# ECAT1__OUT.net
KiCad netlist of a schematic drawn in Altium Designer
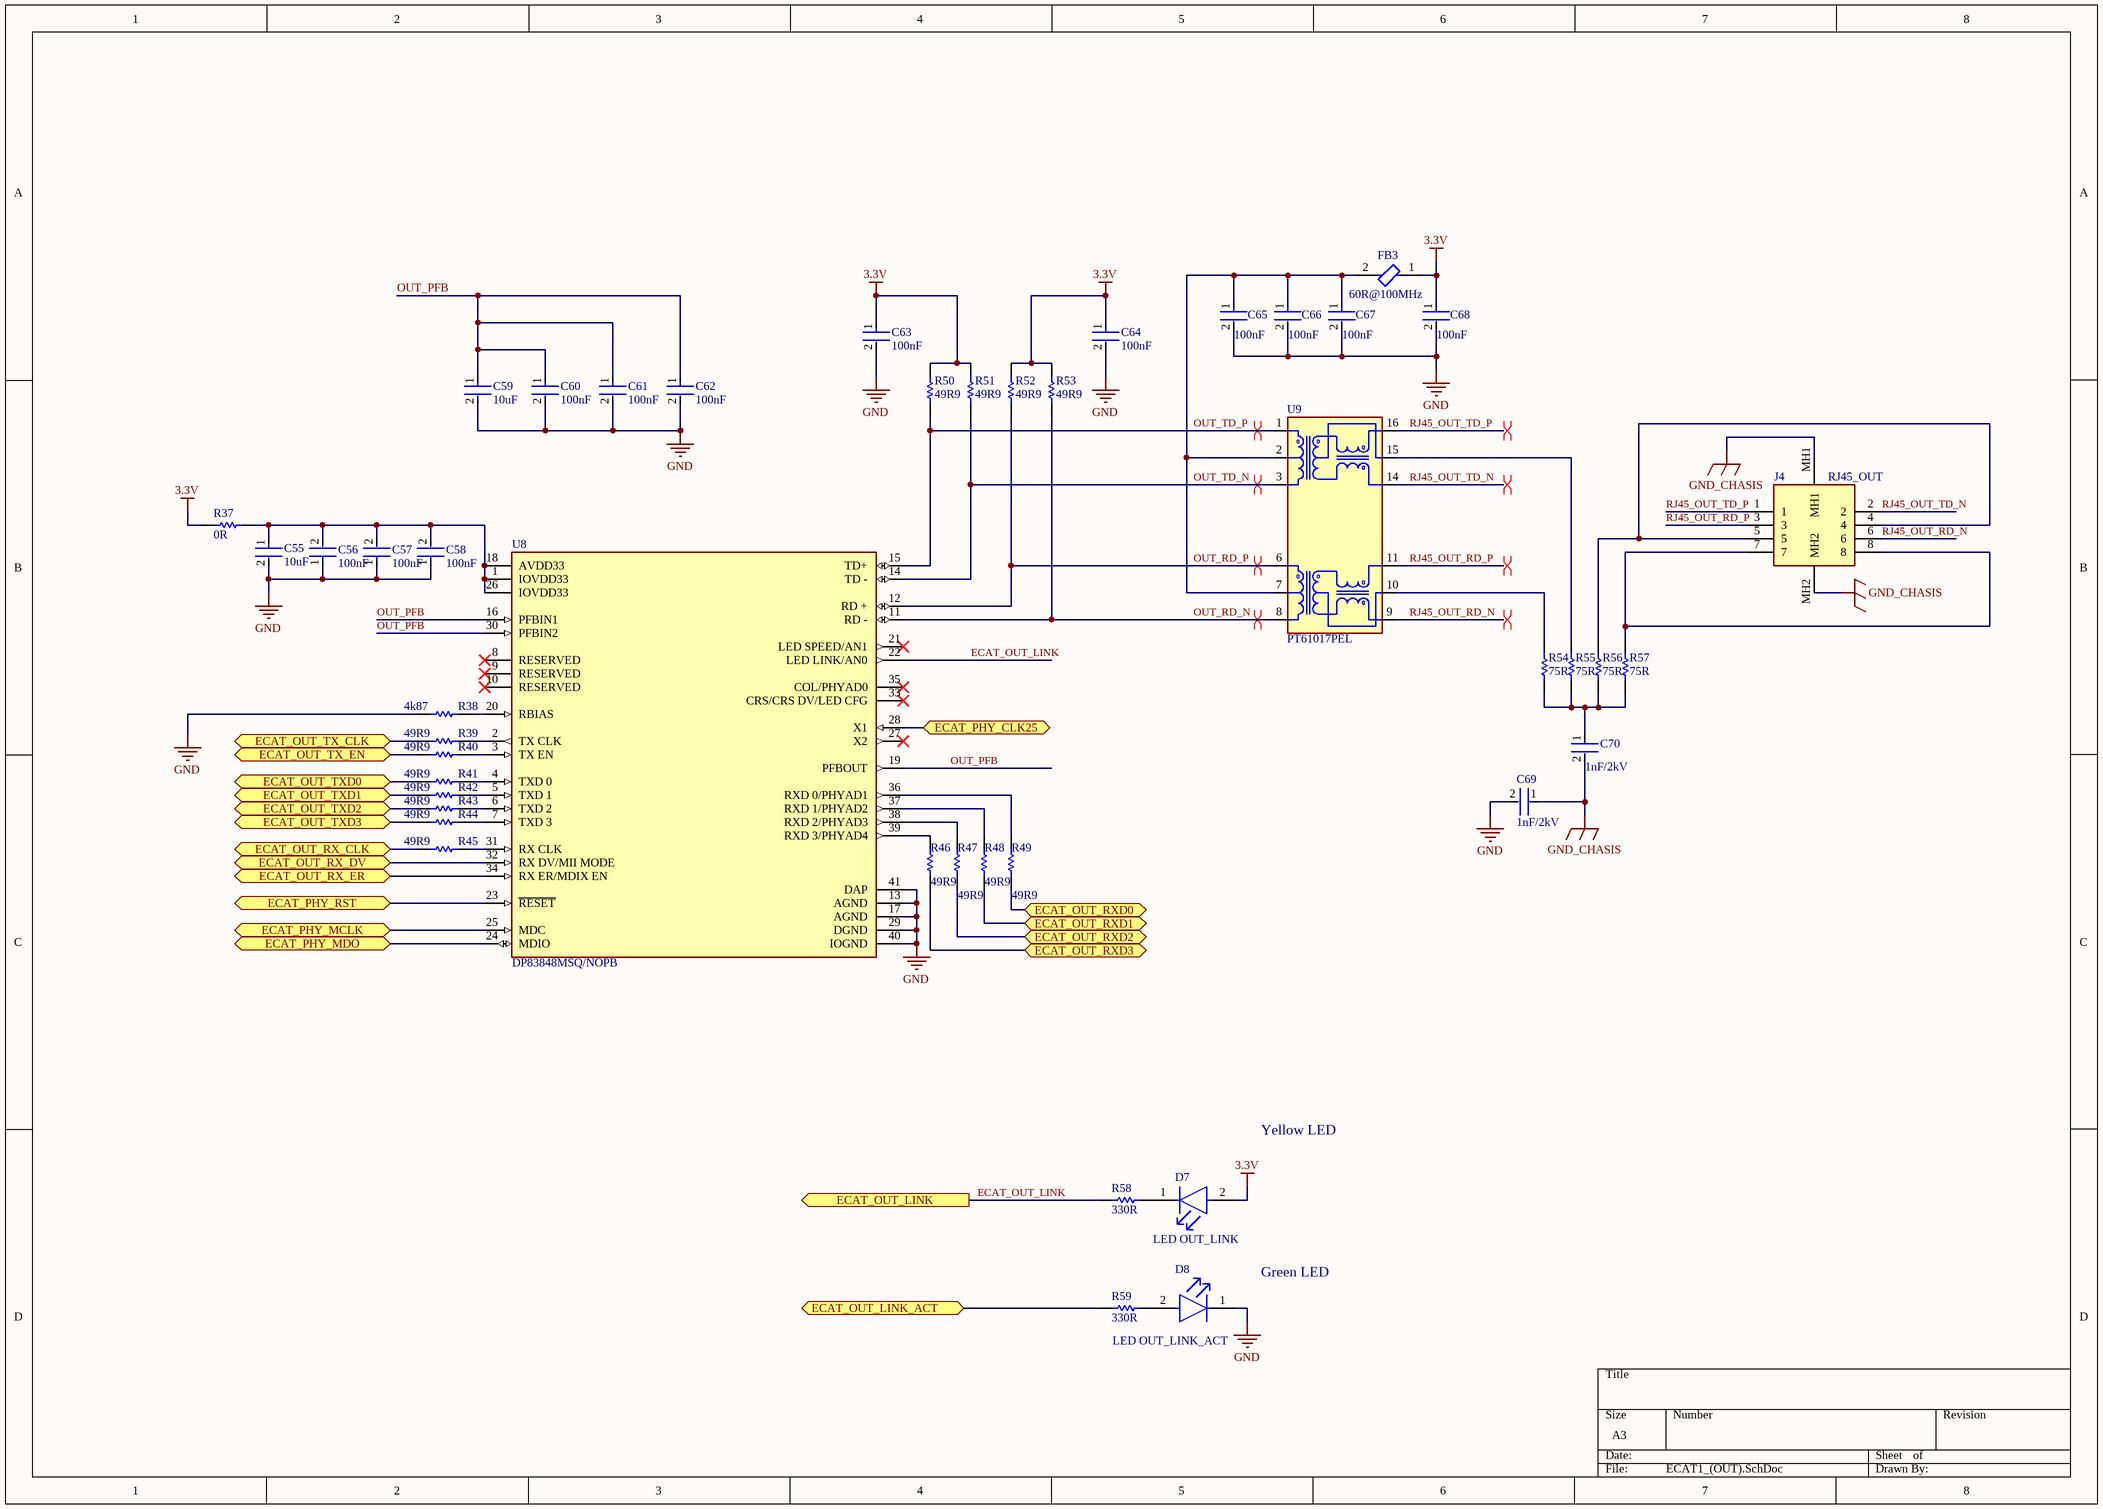
[diagram p0: ECAT1_(OUT).SchDoc]

(export (version "E")
  (design (tool "Eeschema 10.0.6"))
  (components
    (comp (ref "C55")
      (value "10uF")
      (footprint "FP-C0805C-DN-MFG")
      (description "CAP CER 0.1UF 50V X7R 0805")
      (fields
        (field (name "MANUFACTURER PART NUMBER") "C0805C104K5RACTU")
        (field (name "MANUFACTURER") "KEMET")
      )
      (libsource (lib "Altium Content Vault") (part "b4654b650e69147ec39a6b967a45e02"))
    )
    (comp (ref "C56")
      (value "100nF")
      (footprint "FP-C0805C-DN-MFG")
      (description "CAP CER 0.1UF 50V X7R 0805")
      (fields
        (field (name "MANUFACTURER PART NUMBER") "C0805C104K5RACTU")
        (field (name "MANUFACTURER") "KEMET")
      )
      (libsource (lib "Altium Content Vault") (part "b4654b650e69147ec39a6b967a45e02"))
    )
    (comp (ref "C57")
      (value "100nF")
      (footprint "FP-C0805C-DN-MFG")
      (description "CAP CER 0.1UF 50V X7R 0805")
      (fields
        (field (name "MANUFACTURER PART NUMBER") "C0805C104K5RACTU")
        (field (name "MANUFACTURER") "KEMET")
      )
      (libsource (lib "Altium Content Vault") (part "b4654b650e69147ec39a6b967a45e02"))
    )
    (comp (ref "C58")
      (value "100nF")
      (footprint "FP-C0805C-DN-MFG")
      (description "CAP CER 0.1UF 50V X7R 0805")
      (fields
        (field (name "MANUFACTURER PART NUMBER") "C0805C104K5RACTU")
        (field (name "MANUFACTURER") "KEMET")
      )
      (libsource (lib "Altium Content Vault") (part "b4654b650e69147ec39a6b967a45e02"))
    )
    (comp (ref "C59")
      (value "10uF")
      (footprint "FP-C0805C-DN-MFG")
      (description "CAP CER 0.1UF 50V X7R 0805")
      (fields
        (field (name "MANUFACTURER PART NUMBER") "C0805C104K5RACTU")
        (field (name "MANUFACTURER") "KEMET")
      )
      (libsource (lib "Altium Content Vault") (part "b4654b650e69147ec39a6b967a45e02"))
    )
    (comp (ref "C60")
      (value "100nF")
      (footprint "FP-C0805C-DN-MFG")
      (description "CAP CER 0.1UF 50V X7R 0805")
      (fields
        (field (name "MANUFACTURER PART NUMBER") "C0805C104K5RACTU")
        (field (name "MANUFACTURER") "KEMET")
      )
      (libsource (lib "Altium Content Vault") (part "b4654b650e69147ec39a6b967a45e02"))
    )
    (comp (ref "C61")
      (value "100nF")
      (footprint "FP-C0805C-DN-MFG")
      (description "CAP CER 0.1UF 50V X7R 0805")
      (fields
        (field (name "MANUFACTURER PART NUMBER") "C0805C104K5RACTU")
        (field (name "MANUFACTURER") "KEMET")
      )
      (libsource (lib "Altium Content Vault") (part "b4654b650e69147ec39a6b967a45e02"))
    )
    (comp (ref "C62")
      (value "100nF")
      (footprint "FP-C0805C-DN-MFG")
      (description "CAP CER 0.1UF 50V X7R 0805")
      (fields
        (field (name "MANUFACTURER PART NUMBER") "C0805C104K5RACTU")
        (field (name "MANUFACTURER") "KEMET")
      )
      (libsource (lib "Altium Content Vault") (part "b4654b650e69147ec39a6b967a45e02"))
    )
    (comp (ref "C63")
      (value "100nF")
      (footprint "FP-C0805C-DN-MFG")
      (description "CAP CER 0.1UF 50V X7R 0805")
      (fields
        (field (name "MANUFACTURER PART NUMBER") "C0805C104K5RACTU")
        (field (name "MANUFACTURER") "KEMET")
      )
      (libsource (lib "Altium Content Vault") (part "b4654b650e69147ec39a6b967a45e02"))
    )
    (comp (ref "C64")
      (value "100nF")
      (footprint "FP-C0805C-DN-MFG")
      (description "CAP CER 0.1UF 50V X7R 0805")
      (fields
        (field (name "MANUFACTURER PART NUMBER") "C0805C104K5RACTU")
        (field (name "MANUFACTURER") "KEMET")
      )
      (libsource (lib "Altium Content Vault") (part "b4654b650e69147ec39a6b967a45e02"))
    )
    (comp (ref "C65")
      (value "100nF")
      (footprint "FP-C0805C-DN-MFG")
      (description "CAP CER 0.1UF 50V X7R 0805")
      (fields
        (field (name "MANUFACTURER PART NUMBER") "C0805C104K5RACTU")
        (field (name "MANUFACTURER") "KEMET")
      )
      (libsource (lib "Altium Content Vault") (part "b4654b650e69147ec39a6b967a45e02"))
    )
    (comp (ref "C66")
      (value "100nF")
      (footprint "FP-C0805C-DN-MFG")
      (description "CAP CER 0.1UF 50V X7R 0805")
      (fields
        (field (name "MANUFACTURER PART NUMBER") "C0805C104K5RACTU")
        (field (name "MANUFACTURER") "KEMET")
      )
      (libsource (lib "Altium Content Vault") (part "b4654b650e69147ec39a6b967a45e02"))
    )
    (comp (ref "C67")
      (value "100nF")
      (footprint "FP-C0805C-DN-MFG")
      (description "CAP CER 0.1UF 50V X7R 0805")
      (fields
        (field (name "MANUFACTURER PART NUMBER") "C0805C104K5RACTU")
        (field (name "MANUFACTURER") "KEMET")
      )
      (libsource (lib "Altium Content Vault") (part "b4654b650e69147ec39a6b967a45e02"))
    )
    (comp (ref "C68")
      (value "100nF")
      (footprint "FP-C0805C-DN-MFG")
      (description "CAP CER 0.1UF 50V X7R 0805")
      (fields
        (field (name "MANUFACTURER PART NUMBER") "C0805C104K5RACTU")
        (field (name "MANUFACTURER") "KEMET")
      )
      (libsource (lib "Altium Content Vault") (part "b4654b650e69147ec39a6b967a45e02"))
    )
    (comp (ref "C69")
      (value "1nF/2kV")
      (footprint "FP-CC1206-0_3-1_45-IPC_C")
      (description "1nF/2kV/1206")
      (fields (field (name "TOLERANCE") "10%") (field (name "VOLTAGE") "2kV"))
      (libsource (lib "Altium Content Vault") (part "02cd4be3c70576c341d710602a673aa"))
    )
    (comp (ref "C70")
      (value "1nF/2kV")
      (footprint "FP-CC1206-0_3-1_45-IPC_C")
      (description "1nF/2kV/1206")
      (fields (field (name "TOLERANCE") "10%") (field (name "VOLTAGE") "2kV"))
      (libsource (lib "Altium Content Vault") (part "02cd4be3c70576c341d710602a673aa"))
    )
    (comp (ref "D7")
      (value "LED OUT_LINK")
      (footprint "FP-LTST-C191GKT-MFG")
      (description "KPHD-1608LVSYCK")
      (libsource (lib "Altium Content Vault") (part "8706943c75ba83719d021d2fdc84c58"))
    )
    (comp (ref "D8")
      (value "LED OUT_LINK_ACT")
      (footprint "FP-LTST-C191GKT-MFG")
      (description "KPHD-1608LVCGCK")
      (libsource (lib "Altium Content Vault") (part "8706943c75ba83719d021d2fdc84c58"))
    )
    (comp (ref "FB3")
      (value "60R@100MHz")
      (footprint "FP-BLM18-0_15-t0_8-IPC_B")
      (description "Chip Ferrite Bead, 0603, 60Ω @ 100MHz, 0.1Ω, , 1A")
      (fields (field (name "TOLERANCE") "25%"))
      (libsource (lib "Altium Content Vault") (part "5f30dd21d616792df468990f7003faa"))
    )
    (comp (ref "J4")
      (value "RJ45_OUT")
      (footprint "438600010")
      (fields
        (field (name "MOUSER PART NUMBER") "538-43860-0010")
        (field (name "MANUFACTURER_PART_NUMBER") "43860-0010")
      )
      (libsource (lib "43860-0010_RJ45") (part "43860-0010"))
    )
    (comp (ref "R37")
      (value "0R")
      (footprint "RESC1609X50X30NL8T20")
      (description "0603")
      (fields (field (name "MANUFACTURER") "Vishay Semiconductor"))
      (libsource (lib "Altium Content Vault") (part "RES-2"))
    )
    (comp (ref "R38")
      (value "4k87")
      (footprint "RESC2013X50X30LL20T20")
      (description "0805")
      (fields (field (name "MANUFACTURER") "Vishay Dale") (field (name "PART NUMBER") "CRCW08050000Z0EA"))
      (libsource (lib "Altium Content Vault") (part "RES"))
    )
    (comp (ref "R39")
      (value "49R9")
      (footprint "RESC2013X50X30LL20T20")
      (description "0805")
      (fields (field (name "MANUFACTURER") "Vishay Dale") (field (name "PART NUMBER") "CRCW08050000Z0EA"))
      (libsource (lib "Altium Content Vault") (part "RES"))
    )
    (comp (ref "R40")
      (value "49R9")
      (footprint "RESC2013X50X30LL20T20")
      (description "0805")
      (fields (field (name "MANUFACTURER") "Vishay Dale") (field (name "PART NUMBER") "CRCW08050000Z0EA"))
      (libsource (lib "Altium Content Vault") (part "RES"))
    )
    (comp (ref "R41")
      (value "49R9")
      (footprint "RESC2013X50X30LL20T20")
      (description "0805")
      (fields (field (name "MANUFACTURER") "Vishay Dale") (field (name "PART NUMBER") "CRCW08050000Z0EA"))
      (libsource (lib "Altium Content Vault") (part "RES"))
    )
    (comp (ref "R42")
      (value "49R9")
      (footprint "RESC2013X50X30LL20T20")
      (description "0805")
      (fields (field (name "MANUFACTURER") "Vishay Dale") (field (name "PART NUMBER") "CRCW08050000Z0EA"))
      (libsource (lib "Altium Content Vault") (part "RES"))
    )
    (comp (ref "R43")
      (value "49R9")
      (footprint "RESC2013X50X30LL20T20")
      (description "0805")
      (fields (field (name "MANUFACTURER") "Vishay Dale") (field (name "PART NUMBER") "CRCW08050000Z0EA"))
      (libsource (lib "Altium Content Vault") (part "RES"))
    )
    (comp (ref "R44")
      (value "49R9")
      (footprint "RESC2013X50X30LL20T20")
      (description "0805")
      (fields (field (name "MANUFACTURER") "Vishay Dale") (field (name "PART NUMBER") "CRCW08050000Z0EA"))
      (libsource (lib "Altium Content Vault") (part "RES"))
    )
    (comp (ref "R45")
      (value "49R9")
      (footprint "RESC2013X50X30LL20T20")
      (description "0805")
      (fields (field (name "MANUFACTURER") "Vishay Dale") (field (name "PART NUMBER") "CRCW08050000Z0EA"))
      (libsource (lib "Altium Content Vault") (part "RES"))
    )
    (comp (ref "R46")
      (value "49R9")
      (footprint "RESC2013X50X30LL20T20")
      (description "0805")
      (fields (field (name "MANUFACTURER") "Vishay Dale") (field (name "PART NUMBER") "CRCW08050000Z0EA"))
      (libsource (lib "Altium Content Vault") (part "RES"))
    )
    (comp (ref "R47")
      (value "49R9")
      (footprint "RESC2013X50X30LL20T20")
      (description "0805")
      (fields (field (name "MANUFACTURER") "Vishay Dale") (field (name "PART NUMBER") "CRCW08050000Z0EA"))
      (libsource (lib "Altium Content Vault") (part "RES"))
    )
    (comp (ref "R48")
      (value "49R9")
      (footprint "RESC2013X50X30LL20T20")
      (description "0805")
      (fields (field (name "MANUFACTURER") "Vishay Dale") (field (name "PART NUMBER") "CRCW08050000Z0EA"))
      (libsource (lib "Altium Content Vault") (part "RES"))
    )
    (comp (ref "R49")
      (value "49R9")
      (footprint "RESC2013X50X30LL20T20")
      (description "0805")
      (fields (field (name "MANUFACTURER") "Vishay Dale") (field (name "PART NUMBER") "CRCW08050000Z0EA"))
      (libsource (lib "Altium Content Vault") (part "RES"))
    )
    (comp (ref "R50")
      (value "49R9")
      (footprint "RESC2013X50X30LL20T20")
      (description "0805")
      (fields (field (name "MANUFACTURER") "Vishay Dale") (field (name "PART NUMBER") "CRCW08050000Z0EA"))
      (libsource (lib "Altium Content Vault") (part "RES"))
    )
    (comp (ref "R51")
      (value "49R9")
      (footprint "RESC2013X50X30LL20T20")
      (description "0805")
      (fields (field (name "MANUFACTURER") "Vishay Dale") (field (name "PART NUMBER") "CRCW08050000Z0EA"))
      (libsource (lib "Altium Content Vault") (part "RES"))
    )
    (comp (ref "R52")
      (value "49R9")
      (footprint "RESC2013X50X30LL20T20")
      (description "0805")
      (fields (field (name "MANUFACTURER") "Vishay Dale") (field (name "PART NUMBER") "CRCW08050000Z0EA"))
      (libsource (lib "Altium Content Vault") (part "RES"))
    )
    (comp (ref "R53")
      (value "49R9")
      (footprint "RESC2013X50X30LL20T20")
      (description "0805")
      (fields (field (name "MANUFACTURER") "Vishay Dale") (field (name "PART NUMBER") "CRCW08050000Z0EA"))
      (libsource (lib "Altium Content Vault") (part "RES"))
    )
    (comp (ref "R54")
      (value "75R")
      (footprint "RESC2013X50X30LL20T20")
      (description "0805")
      (fields (field (name "MANUFACTURER") "Vishay Dale") (field (name "PART NUMBER") "CRCW08050000Z0EA"))
      (libsource (lib "Altium Content Vault") (part "RES"))
    )
    (comp (ref "R55")
      (value "75R")
      (footprint "RESC2013X50X30LL20T20")
      (description "0805")
      (fields (field (name "MANUFACTURER") "Vishay Dale") (field (name "PART NUMBER") "CRCW08050000Z0EA"))
      (libsource (lib "Altium Content Vault") (part "RES"))
    )
    (comp (ref "R56")
      (value "75R")
      (footprint "RESC2013X50X30LL20T20")
      (description "0805")
      (fields (field (name "MANUFACTURER") "Vishay Dale") (field (name "PART NUMBER") "CRCW08050000Z0EA"))
      (libsource (lib "Altium Content Vault") (part "RES"))
    )
    (comp (ref "R57")
      (value "75R")
      (footprint "RESC2013X50X30LL20T20")
      (description "0805")
      (fields (field (name "MANUFACTURER") "Vishay Dale") (field (name "PART NUMBER") "CRCW08050000Z0EA"))
      (libsource (lib "Altium Content Vault") (part "RES"))
    )
    (comp (ref "R58")
      (value "330R")
      (footprint "RESC2013X50X30LL20T20")
      (description "0805")
      (fields (field (name "MANUFACTURER") "Vishay Dale") (field (name "PART NUMBER") "CRCW08050000Z0EA"))
      (libsource (lib "Altium Content Vault") (part "RES"))
    )
    (comp (ref "R59")
      (value "330R")
      (footprint "RESC2013X50X30LL20T20")
      (description "0805")
      (fields (field (name "MANUFACTURER") "Vishay Dale") (field (name "PART NUMBER") "CRCW08050000Z0EA"))
      (libsource (lib "Altium Content Vault") (part "RES"))
    )
    (comp (ref "U8")
      (value "DP83848MSQ/NOPB")
      (footprint "FP-RTA0040A-IPC_B")
      (description "IC TRANSCEIVER 1/1 40WQFN")
      (libsource (lib "Altium Content Vault") (part "3c06b58cd6473fc695b5b7b70754a9c"))
    )
    (comp (ref "U9")
      (value "PT61017PEL")
      (footprint "PT61017PEL")
      (description "350 µH LAN 10/100 Base-T Pulse Transformer 1CT:1CT Surface Mount\r\n\r\nPT61017PEL")
      (fields (field (name "MF") "Bourns"))
      (libsource (lib "OTHER") (part "PT61017PEL"))
    )
  )
  (nets
    (net (code "1") (name "/ECAT_OUT_LINK") (class "Default")
      (node (ref "R58") (pin "1") (pinfunction "1_1") (pintype "passive"))
      (node (ref "U8") (pin "22") (pinfunction "LED_LINK/AN0_22") (pintype "output"))
    )
    (net (code "2") (name "/ECAT_OUT_LINK_ACT") (class "Default")
      (node (ref "R59") (pin "1") (pinfunction "1_1") (pintype "passive"))
    )
    (net (code "3") (name "/ECAT_OUT_RXD0") (class "Default")
      (node (ref "R49") (pin "1") (pinfunction "1_1") (pintype "passive"))
    )
    (net (code "4") (name "/ECAT_OUT_RXD1") (class "Default")
      (node (ref "R48") (pin "1") (pinfunction "1_1") (pintype "passive"))
    )
    (net (code "5") (name "/ECAT_OUT_RXD2") (class "Default")
      (node (ref "R47") (pin "1") (pinfunction "1_1") (pintype "passive"))
    )
    (net (code "6") (name "/ECAT_OUT_RXD3") (class "Default")
      (node (ref "R46") (pin "1") (pinfunction "1_1") (pintype "passive"))
    )
    (net (code "7") (name "/ECAT_OUT_RX_CLK") (class "Default")
      (node (ref "R45") (pin "1") (pinfunction "1_1") (pintype "passive"))
    )
    (net (code "8") (name "/ECAT_OUT_RX_DV") (class "Default")
      (node (ref "U8") (pin "32") (pinfunction "RX_DV/MII_MODE_32") (pintype "input"))
    )
    (net (code "9") (name "/ECAT_OUT_RX_ER") (class "Default")
      (node (ref "U8") (pin "34") (pinfunction "RX_ER/MDIX_EN_34") (pintype "input"))
    )
    (net (code "10") (name "/ECAT_OUT_TXD0") (class "Default")
      (node (ref "R41") (pin "1") (pinfunction "1_1") (pintype "passive"))
    )
    (net (code "11") (name "/ECAT_OUT_TXD1") (class "Default")
      (node (ref "R42") (pin "1") (pinfunction "1_1") (pintype "passive"))
    )
    (net (code "12") (name "/ECAT_OUT_TXD2") (class "Default")
      (node (ref "R43") (pin "1") (pinfunction "1_1") (pintype "passive"))
    )
    (net (code "13") (name "/ECAT_OUT_TXD3") (class "Default")
      (node (ref "R44") (pin "1") (pinfunction "1_1") (pintype "passive"))
    )
    (net (code "14") (name "/ECAT_OUT_TX_CLK") (class "Default")
      (node (ref "R39") (pin "1") (pinfunction "1_1") (pintype "passive"))
    )
    (net (code "15") (name "/ECAT_OUT_TX_EN") (class "Default")
      (node (ref "R40") (pin "1") (pinfunction "1_1") (pintype "passive"))
    )
    (net (code "16") (name "/ECAT_PHY_CLK25") (class "Default")
      (node (ref "U8") (pin "28") (pinfunction "X1_28") (pintype "input"))
    )
    (net (code "17") (name "/ECAT_PHY_MCLK") (class "Default")
      (node (ref "U8") (pin "25") (pinfunction "MDC_25") (pintype "input"))
    )
    (net (code "18") (name "/ECAT_PHY_MDO") (class "Default")
      (node (ref "U8") (pin "24") (pinfunction "MDIO_24") (pintype "bidirectional"))
    )
    (net (code "19") (name "/ECAT_PHY_RST") (class "Default")
      (node (ref "U8") (pin "23") (pinfunction "~{RESET}_23") (pintype "input"))
    )
    (net (code "20") (name "/OUT_PFB") (class "Default")
      (node (ref "C59") (pin "1") (pinfunction "1_1") (pintype "passive"))
      (node (ref "C60") (pin "1") (pinfunction "1_1") (pintype "passive"))
      (node (ref "C61") (pin "1") (pinfunction "1_1") (pintype "passive"))
      (node (ref "C62") (pin "1") (pinfunction "1_1") (pintype "passive"))
      (node (ref "U8") (pin "16") (pinfunction "PFBIN1_16") (pintype "input"))
      (node (ref "U8") (pin "19") (pinfunction "PFBOUT_19") (pintype "output"))
      (node (ref "U8") (pin "30") (pinfunction "PFBIN2_30") (pintype "input"))
    )
    (net (code "21") (name "/OUT_RD_N") (class "Default")
      (node (ref "R53") (pin "1") (pinfunction "1_1") (pintype "passive"))
      (node (ref "U8") (pin "11") (pinfunction "RD_-_11") (pintype "bidirectional"))
      (node (ref "U9") (pin "8") (pinfunction "8_8") (pintype "passive"))
    )
    (net (code "22") (name "/OUT_RD_P") (class "Default")
      (node (ref "R52") (pin "1") (pinfunction "1_1") (pintype "passive"))
      (node (ref "U8") (pin "12") (pinfunction "RD_+_12") (pintype "bidirectional"))
      (node (ref "U9") (pin "6") (pinfunction "6_6") (pintype "passive"))
    )
    (net (code "23") (name "/OUT_TD_N") (class "Default")
      (node (ref "R51") (pin "1") (pinfunction "1_1") (pintype "passive"))
      (node (ref "U8") (pin "14") (pinfunction "TD_-_14") (pintype "bidirectional"))
      (node (ref "U9") (pin "3") (pinfunction "3_3") (pintype "passive"))
    )
    (net (code "24") (name "/OUT_TD_P") (class "Default")
      (node (ref "R50") (pin "1") (pinfunction "1_1") (pintype "passive"))
      (node (ref "U8") (pin "15") (pinfunction "TD+_15") (pintype "bidirectional"))
      (node (ref "U9") (pin "1") (pinfunction "1_1") (pintype "passive"))
    )
    (net (code "25") (name "/RJ45_OUT_RD_N") (class "Default")
      (node (ref "J4") (pin "6") (pinfunction "6_6") (pintype "passive"))
      (node (ref "U9") (pin "9") (pinfunction "9_9") (pintype "passive"))
    )
    (net (code "26") (name "/RJ45_OUT_RD_P") (class "Default")
      (node (ref "J4") (pin "3") (pinfunction "3_3") (pintype "passive"))
      (node (ref "U9") (pin "11") (pinfunction "11_11") (pintype "passive"))
    )
    (net (code "27") (name "/RJ45_OUT_TD_N") (class "Default")
      (node (ref "J4") (pin "2") (pinfunction "2_2") (pintype "passive"))
      (node (ref "U9") (pin "14") (pinfunction "14_14") (pintype "passive"))
    )
    (net (code "28") (name "/RJ45_OUT_TD_P") (class "Default")
      (node (ref "J4") (pin "1") (pinfunction "1_1") (pintype "passive"))
      (node (ref "U9") (pin "16") (pinfunction "16_16") (pintype "passive"))
    )
    (net (code "29") (name "3.3V") (class "Default")
      (node (ref "C63") (pin "1") (pinfunction "1_1") (pintype "passive"))
      (node (ref "C64") (pin "1") (pinfunction "1_1") (pintype "passive"))
      (node (ref "C68") (pin "1") (pinfunction "1_1") (pintype "passive"))
      (node (ref "D7") (pin "2") (pinfunction "A_2") (pintype "passive"))
      (node (ref "FB3") (pin "1") (pinfunction "1_1") (pintype "passive"))
      (node (ref "R37") (pin "2") (pinfunction "2_2") (pintype "passive"))
      (node (ref "R50") (pin "2") (pinfunction "2_2") (pintype "passive"))
      (node (ref "R51") (pin "2") (pinfunction "2_2") (pintype "passive"))
      (node (ref "R52") (pin "2") (pinfunction "2_2") (pintype "passive"))
      (node (ref "R53") (pin "2") (pinfunction "2_2") (pintype "passive"))
    )
    (net (code "30") (name "GND") (class "Default")
      (node (ref "C55") (pin "2") (pinfunction "2_2") (pintype "passive"))
      (node (ref "C56") (pin "1") (pinfunction "1_1") (pintype "passive"))
      (node (ref "C57") (pin "1") (pinfunction "1_1") (pintype "passive"))
      (node (ref "C58") (pin "1") (pinfunction "1_1") (pintype "passive"))
      (node (ref "C59") (pin "2") (pinfunction "2_2") (pintype "passive"))
      (node (ref "C60") (pin "2") (pinfunction "2_2") (pintype "passive"))
      (node (ref "C61") (pin "2") (pinfunction "2_2") (pintype "passive"))
      (node (ref "C62") (pin "2") (pinfunction "2_2") (pintype "passive"))
      (node (ref "C63") (pin "2") (pinfunction "2_2") (pintype "passive"))
      (node (ref "C64") (pin "2") (pinfunction "2_2") (pintype "passive"))
      (node (ref "C65") (pin "2") (pinfunction "2_2") (pintype "passive"))
      (node (ref "C66") (pin "2") (pinfunction "2_2") (pintype "passive"))
      (node (ref "C67") (pin "2") (pinfunction "2_2") (pintype "passive"))
      (node (ref "C68") (pin "2") (pinfunction "2_2") (pintype "passive"))
      (node (ref "C69") (pin "2") (pinfunction "2_2") (pintype "passive"))
      (node (ref "D8") (pin "1") (pinfunction "C_1") (pintype "passive"))
      (node (ref "R38") (pin "1") (pinfunction "1_1") (pintype "passive"))
      (node (ref "U8") (pin "13") (pinfunction "AGND_13") (pintype "power_in"))
      (node (ref "U8") (pin "17") (pinfunction "AGND_17") (pintype "power_in"))
      (node (ref "U8") (pin "29") (pinfunction "DGND_29") (pintype "power_in"))
      (node (ref "U8") (pin "40") (pinfunction "IOGND_40") (pintype "power_in"))
      (node (ref "U8") (pin "41") (pinfunction "DAP_41") (pintype "power_in"))
    )
    (net (code "31") (name "GND_CHASIS") (class "Default")
      (node (ref "C69") (pin "1") (pinfunction "1_1") (pintype "passive"))
      (node (ref "C70") (pin "2") (pinfunction "2_2") (pintype "passive"))
      (node (ref "J4") (pin "MH1") (pinfunction "MH1_MH1") (pintype "passive"))
      (node (ref "J4") (pin "MH2") (pinfunction "MH2_MH2") (pintype "passive"))
    )
    (net (code "32") (name "Net-(C65-Pad1)") (class "Default")
      (node (ref "C65") (pin "1") (pinfunction "1_1") (pintype "passive"))
      (node (ref "C66") (pin "1") (pinfunction "1_1") (pintype "passive"))
      (node (ref "C67") (pin "1") (pinfunction "1_1") (pintype "passive"))
      (node (ref "FB3") (pin "2") (pinfunction "2_2") (pintype "passive"))
      (node (ref "U9") (pin "2") (pinfunction "2_2") (pintype "passive"))
      (node (ref "U9") (pin "7") (pinfunction "7_7") (pintype "passive"))
    )
    (net (code "33") (name "Net-(C70-Pad1)") (class "Default")
      (node (ref "C70") (pin "1") (pinfunction "1_1") (pintype "passive"))
      (node (ref "R54") (pin "1") (pinfunction "1_1") (pintype "passive"))
      (node (ref "R55") (pin "1") (pinfunction "1_1") (pintype "passive"))
      (node (ref "R56") (pin "1") (pinfunction "1_1") (pintype "passive"))
      (node (ref "R57") (pin "1") (pinfunction "1_1") (pintype "passive"))
    )
    (net (code "34") (name "Net-(D7-C)") (class "Default")
      (node (ref "D7") (pin "1") (pinfunction "C_1") (pintype "passive"))
      (node (ref "R58") (pin "2") (pinfunction "2_2") (pintype "passive"))
    )
    (net (code "35") (name "Net-(D8-A)") (class "Default")
      (node (ref "D8") (pin "2") (pinfunction "A_2") (pintype "passive"))
      (node (ref "R59") (pin "2") (pinfunction "2_2") (pintype "passive"))
    )
    (net (code "36") (name "Net-(J4-Pad4)") (class "Default")
      (node (ref "J4") (pin "4") (pinfunction "4_4") (pintype "passive"))
      (node (ref "J4") (pin "5") (pinfunction "5_5") (pintype "passive"))
      (node (ref "R56") (pin "2") (pinfunction "2_2") (pintype "passive"))
    )
    (net (code "37") (name "Net-(J4-Pad7)") (class "Default")
      (node (ref "J4") (pin "7") (pinfunction "7_7") (pintype "passive"))
      (node (ref "J4") (pin "8") (pinfunction "8_8") (pintype "passive"))
      (node (ref "R57") (pin "2") (pinfunction "2_2") (pintype "passive"))
    )
    (net (code "38") (name "Net-(R54-Pad2)") (class "Default")
      (node (ref "R54") (pin "2") (pinfunction "2_2") (pintype "passive"))
      (node (ref "U9") (pin "10") (pinfunction "10_10") (pintype "passive"))
    )
    (net (code "39") (name "Net-(R55-Pad2)") (class "Default")
      (node (ref "R55") (pin "2") (pinfunction "2_2") (pintype "passive"))
      (node (ref "U9") (pin "15") (pinfunction "15_15") (pintype "passive"))
    )
    (net (code "40") (name "Net-(U8-AVDD33)") (class "Default")
      (node (ref "C55") (pin "1") (pinfunction "1_1") (pintype "passive"))
      (node (ref "C56") (pin "2") (pinfunction "2_2") (pintype "passive"))
      (node (ref "C57") (pin "2") (pinfunction "2_2") (pintype "passive"))
      (node (ref "C58") (pin "2") (pinfunction "2_2") (pintype "passive"))
      (node (ref "R37") (pin "1") (pinfunction "1_1") (pintype "passive"))
      (node (ref "U8") (pin "1") (pinfunction "IOVDD33_1") (pintype "power_in"))
      (node (ref "U8") (pin "18") (pinfunction "AVDD33_18") (pintype "power_in"))
      (node (ref "U8") (pin "26") (pinfunction "IOVDD33_26") (pintype "power_in"))
    )
    (net (code "41") (name "Net-(U8-RBIAS)") (class "Default")
      (node (ref "R38") (pin "2") (pinfunction "2_2") (pintype "passive"))
      (node (ref "U8") (pin "20") (pinfunction "RBIAS_20") (pintype "input"))
    )
    (net (code "42") (name "Net-(U8-RXD_0{slash}PHYAD1)") (class "Default")
      (node (ref "R49") (pin "2") (pinfunction "2_2") (pintype "passive"))
      (node (ref "U8") (pin "36") (pinfunction "RXD_0/PHYAD1_36") (pintype "output"))
    )
    (net (code "43") (name "Net-(U8-RXD_1{slash}PHYAD2)") (class "Default")
      (node (ref "R48") (pin "2") (pinfunction "2_2") (pintype "passive"))
      (node (ref "U8") (pin "37") (pinfunction "RXD_1/PHYAD2_37") (pintype "output"))
    )
    (net (code "44") (name "Net-(U8-RXD_2{slash}PHYAD3)") (class "Default")
      (node (ref "R47") (pin "2") (pinfunction "2_2") (pintype "passive"))
      (node (ref "U8") (pin "38") (pinfunction "RXD_2/PHYAD3_38") (pintype "output"))
    )
    (net (code "45") (name "Net-(U8-RXD_3{slash}PHYAD4)") (class "Default")
      (node (ref "R46") (pin "2") (pinfunction "2_2") (pintype "passive"))
      (node (ref "U8") (pin "39") (pinfunction "RXD_3/PHYAD4_39") (pintype "output"))
    )
    (net (code "46") (name "Net-(U8-RX_CLK)") (class "Default")
      (node (ref "R45") (pin "2") (pinfunction "2_2") (pintype "passive"))
      (node (ref "U8") (pin "31") (pinfunction "RX_CLK_31") (pintype "input"))
    )
    (net (code "47") (name "Net-(U8-TXD_0)") (class "Default")
      (node (ref "R41") (pin "2") (pinfunction "2_2") (pintype "passive"))
      (node (ref "U8") (pin "4") (pinfunction "TXD_0_4") (pintype "input"))
    )
    (net (code "48") (name "Net-(U8-TXD_1)") (class "Default")
      (node (ref "R42") (pin "2") (pinfunction "2_2") (pintype "passive"))
      (node (ref "U8") (pin "5") (pinfunction "TXD_1_5") (pintype "input"))
    )
    (net (code "49") (name "Net-(U8-TXD_2)") (class "Default")
      (node (ref "R43") (pin "2") (pinfunction "2_2") (pintype "passive"))
      (node (ref "U8") (pin "6") (pinfunction "TXD_2_6") (pintype "input"))
    )
    (net (code "50") (name "Net-(U8-TXD_3)") (class "Default")
      (node (ref "R44") (pin "2") (pinfunction "2_2") (pintype "passive"))
      (node (ref "U8") (pin "7") (pinfunction "TXD_3_7") (pintype "input"))
    )
    (net (code "51") (name "Net-(U8-TX_CLK)") (class "Default")
      (node (ref "R39") (pin "2") (pinfunction "2_2") (pintype "passive"))
      (node (ref "U8") (pin "2") (pinfunction "TX_CLK_2") (pintype "output"))
    )
    (net (code "52") (name "Net-(U8-TX_EN)") (class "Default")
      (node (ref "R40") (pin "2") (pinfunction "2_2") (pintype "passive"))
      (node (ref "U8") (pin "3") (pinfunction "TX_EN_3") (pintype "input"))
    )
    (net (code "53") (name "unconnected-(U8-COL{slash}PHYAD0-Pad35)") (class "Default")
      (node (ref "U8") (pin "35") (pinfunction "COL/PHYAD0_35") (pintype "passive+no_connect"))
    )
    (net (code "54") (name "unconnected-(U8-CRS{slash}CRS_DV{slash}LED_CFG-Pad33)") (class "Default")
      (node (ref "U8") (pin "33") (pinfunction "CRS/CRS_DV/LED_CFG_33") (pintype "passive+no_connect"))
    )
    (net (code "55") (name "unconnected-(U8-LED_SPEED{slash}AN1-Pad21)") (class "Default")
      (node (ref "U8") (pin "21") (pinfunction "LED_SPEED/AN1_21") (pintype "output+no_connect"))
    )
    (net (code "56") (name "unconnected-(U8-RESERVED-Pad8)") (class "Default")
      (node (ref "U8") (pin "8") (pinfunction "RESERVED_8") (pintype "passive+no_connect"))
    )
    (net (code "57") (name "unconnected-(U8-RESERVED-Pad9)") (class "Default")
      (node (ref "U8") (pin "9") (pinfunction "RESERVED_9") (pintype "passive+no_connect"))
    )
    (net (code "58") (name "unconnected-(U8-RESERVED-Pad10)") (class "Default")
      (node (ref "U8") (pin "10") (pinfunction "RESERVED_10") (pintype "passive+no_connect"))
    )
    (net (code "59") (name "unconnected-(U8-X2-Pad27)") (class "Default")
      (node (ref "U8") (pin "27") (pinfunction "X2_27") (pintype "output+no_connect"))
    )
  )
)
